# Main.net
KiCad netlist of a schematic drawn in Altium Designer
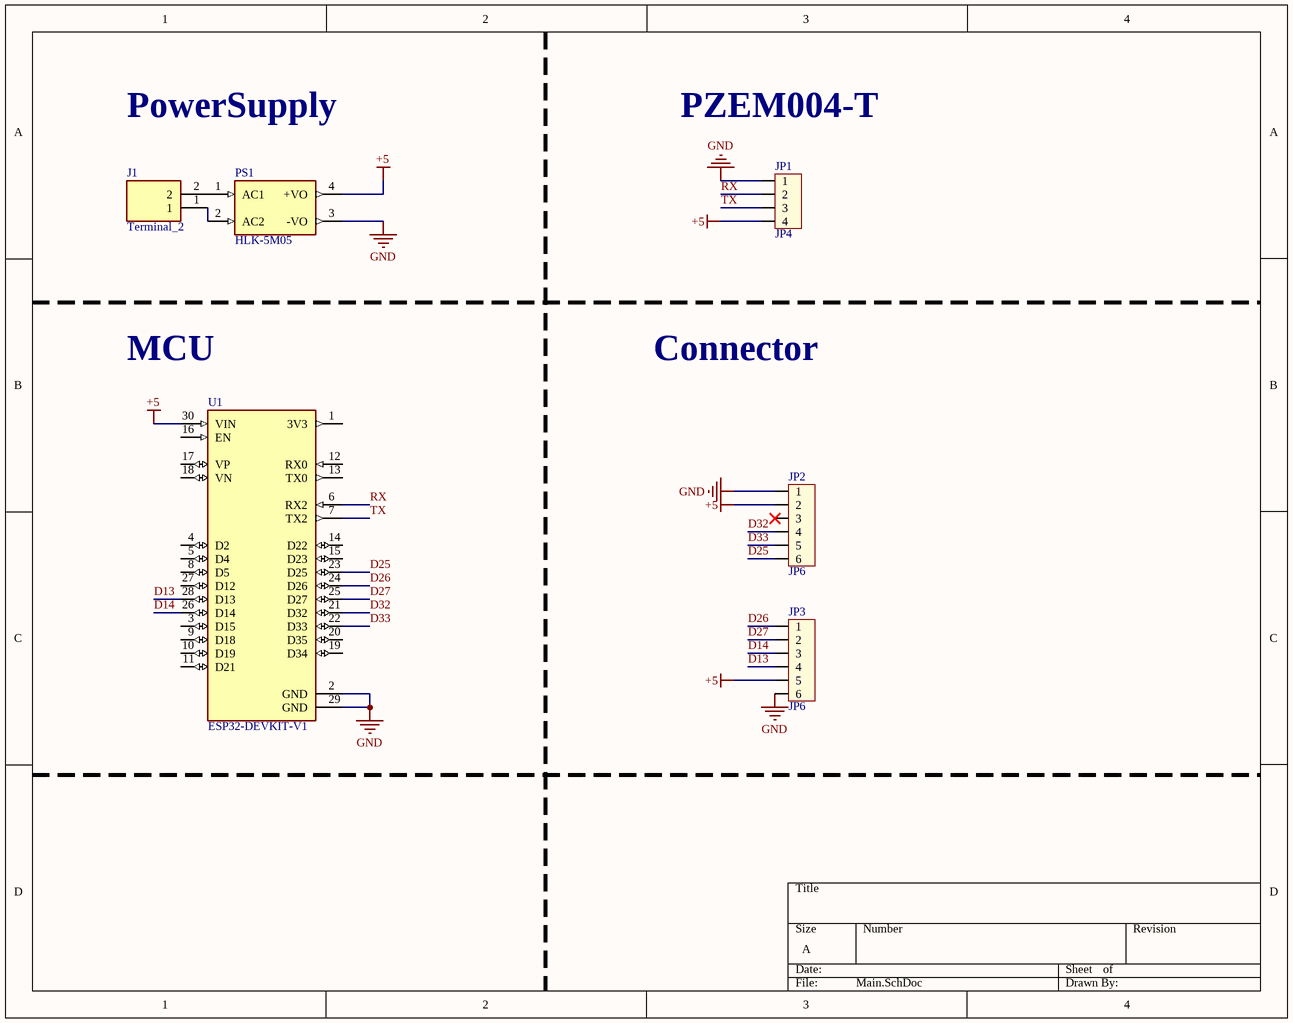
[diagram p0: Main.SchDoc]

(export (version "E")
  (design (tool "Eeschema 10.0.6"))
  (components
    (comp (ref "J1")
      (value "Terminal_2")
      (footprint "TE_282843-2")
      (fields (field (name "MP") "282843-2") (field (name "MF") "{'manufacturer': 'TE Connectivity'}"))
      (libsource (lib "282843-2") (part "282843-2"))
    )
    (comp (ref "JP1")
      (value "JP4")
      (footprint "CON4")
      (description "Connector 4")
      (libsource (lib "Kiet") (part "Con4"))
    )
    (comp (ref "JP2")
      (value "JP6")
      (footprint "CON6")
      (description "Connector 6")
      (libsource (lib "Kiet") (part "Con6"))
    )
    (comp (ref "JP3")
      (value "JP6")
      (footprint "CON6")
      (description "Connector 6")
      (libsource (lib "Kiet") (part "Con6"))
    )
    (comp (ref "PS1")
      (value "HLK-5M05")
      (footprint "CONV_HLK-5M05")
      (description "AC DC 220V to 5V 5W 5Watt Isolated Switching Step-Down Power Supply Module Converter")
      (fields (field (name "MF") "Hi-link"))
      (libsource (lib "HLK-5M05") (part "HLK-5M05"))
    )
    (comp (ref "U1")
      (value "ESP32-DEVKIT-V1")
      (footprint "MODULE_ESP32_DEVKIT_V1")
      (fields (field (name "MF") "Do it"))
      (libsource (lib "ESP32-DEVKIT-V1") (part "ESP32-DEVKIT-V1"))
    )
  )
  (nets
    (net (code "1") (name "+5") (class "Default")
      (node (ref "JP1") (pin "4") (pinfunction "4_4") (pintype "passive"))
      (node (ref "JP2") (pin "2") (pinfunction "2_2") (pintype "passive"))
      (node (ref "JP3") (pin "5") (pinfunction "5_5") (pintype "passive"))
      (node (ref "PS1") (pin "4") (pinfunction "+VO_4") (pintype "output"))
      (node (ref "U1") (pin "30") (pinfunction "VIN_30") (pintype "input"))
    )
    (net (code "2") (name "/D13") (class "Default")
      (node (ref "JP3") (pin "4") (pinfunction "4_4") (pintype "passive"))
      (node (ref "U1") (pin "28") (pinfunction "D13_28") (pintype "bidirectional"))
    )
    (net (code "3") (name "/D14") (class "Default")
      (node (ref "JP3") (pin "3") (pinfunction "3_3") (pintype "passive"))
      (node (ref "U1") (pin "26") (pinfunction "D14_26") (pintype "bidirectional"))
    )
    (net (code "4") (name "/D25") (class "Default")
      (node (ref "JP2") (pin "6") (pinfunction "6_6") (pintype "passive"))
      (node (ref "U1") (pin "23") (pinfunction "D25_23") (pintype "bidirectional"))
    )
    (net (code "5") (name "/D26") (class "Default")
      (node (ref "JP3") (pin "1") (pinfunction "1_1") (pintype "passive"))
      (node (ref "U1") (pin "24") (pinfunction "D26_24") (pintype "bidirectional"))
    )
    (net (code "6") (name "/D27") (class "Default")
      (node (ref "JP3") (pin "2") (pinfunction "2_2") (pintype "passive"))
      (node (ref "U1") (pin "25") (pinfunction "D27_25") (pintype "bidirectional"))
    )
    (net (code "7") (name "/D32") (class "Default")
      (node (ref "JP2") (pin "4") (pinfunction "4_4") (pintype "passive"))
      (node (ref "U1") (pin "21") (pinfunction "D32_21") (pintype "bidirectional"))
    )
    (net (code "8") (name "/D33") (class "Default")
      (node (ref "JP2") (pin "5") (pinfunction "5_5") (pintype "passive"))
      (node (ref "U1") (pin "22") (pinfunction "D33_22") (pintype "bidirectional"))
    )
    (net (code "9") (name "/RX") (class "Default")
      (node (ref "JP1") (pin "2") (pinfunction "2_2") (pintype "passive"))
      (node (ref "U1") (pin "6") (pinfunction "RX2_6") (pintype "input"))
    )
    (net (code "10") (name "/TX") (class "Default")
      (node (ref "JP1") (pin "3") (pinfunction "3_3") (pintype "passive"))
      (node (ref "U1") (pin "7") (pinfunction "TX2_7") (pintype "output"))
    )
    (net (code "11") (name "GND") (class "Default")
      (node (ref "JP1") (pin "1") (pinfunction "1_1") (pintype "passive"))
      (node (ref "JP2") (pin "1") (pinfunction "1_1") (pintype "passive"))
      (node (ref "JP3") (pin "6") (pinfunction "6_6") (pintype "passive"))
      (node (ref "PS1") (pin "3") (pinfunction "-VO_3") (pintype "output"))
      (node (ref "U1") (pin "2") (pinfunction "GND_2") (pintype "power_in"))
      (node (ref "U1") (pin "29") (pinfunction "GND_29") (pintype "power_in"))
    )
    (net (code "12") (name "Net-(PS1-AC1)") (class "Default")
      (node (ref "J1") (pin "2") (pinfunction "2_2") (pintype "passive"))
      (node (ref "PS1") (pin "1") (pinfunction "AC1_1") (pintype "input"))
    )
    (net (code "13") (name "Net-(PS1-AC2)") (class "Default")
      (node (ref "J1") (pin "1") (pinfunction "1_1") (pintype "passive"))
      (node (ref "PS1") (pin "2") (pinfunction "AC2_2") (pintype "input"))
    )
    (net (code "14") (name "unconnected-(JP2-Pad3)") (class "Default")
      (node (ref "JP2") (pin "3") (pinfunction "3_3") (pintype "passive+no_connect"))
    )
    (net (code "15") (name "unconnected-(U1-3V3-Pad1)") (class "Default")
      (node (ref "U1") (pin "1") (pinfunction "3V3_1") (pintype "output"))
    )
    (net (code "16") (name "unconnected-(U1-D2-Pad4)") (class "Default")
      (node (ref "U1") (pin "4") (pinfunction "D2_4") (pintype "bidirectional"))
    )
    (net (code "17") (name "unconnected-(U1-D4-Pad5)") (class "Default")
      (node (ref "U1") (pin "5") (pinfunction "D4_5") (pintype "bidirectional"))
    )
    (net (code "18") (name "unconnected-(U1-D5-Pad8)") (class "Default")
      (node (ref "U1") (pin "8") (pinfunction "D5_8") (pintype "bidirectional"))
    )
    (net (code "19") (name "unconnected-(U1-D12-Pad27)") (class "Default")
      (node (ref "U1") (pin "27") (pinfunction "D12_27") (pintype "bidirectional"))
    )
    (net (code "20") (name "unconnected-(U1-D15-Pad3)") (class "Default")
      (node (ref "U1") (pin "3") (pinfunction "D15_3") (pintype "bidirectional"))
    )
    (net (code "21") (name "unconnected-(U1-D18-Pad9)") (class "Default")
      (node (ref "U1") (pin "9") (pinfunction "D18_9") (pintype "bidirectional"))
    )
    (net (code "22") (name "unconnected-(U1-D19-Pad10)") (class "Default")
      (node (ref "U1") (pin "10") (pinfunction "D19_10") (pintype "bidirectional"))
    )
    (net (code "23") (name "unconnected-(U1-D21-Pad11)") (class "Default")
      (node (ref "U1") (pin "11") (pinfunction "D21_11") (pintype "bidirectional"))
    )
    (net (code "24") (name "unconnected-(U1-D22-Pad14)") (class "Default")
      (node (ref "U1") (pin "14") (pinfunction "D22_14") (pintype "bidirectional"))
    )
    (net (code "25") (name "unconnected-(U1-D23-Pad15)") (class "Default")
      (node (ref "U1") (pin "15") (pinfunction "D23_15") (pintype "bidirectional"))
    )
    (net (code "26") (name "unconnected-(U1-D34-Pad19)") (class "Default")
      (node (ref "U1") (pin "19") (pinfunction "D34_19") (pintype "bidirectional"))
    )
    (net (code "27") (name "unconnected-(U1-D35-Pad20)") (class "Default")
      (node (ref "U1") (pin "20") (pinfunction "D35_20") (pintype "bidirectional"))
    )
    (net (code "28") (name "unconnected-(U1-EN-Pad16)") (class "Default")
      (node (ref "U1") (pin "16") (pinfunction "EN_16") (pintype "input"))
    )
    (net (code "29") (name "unconnected-(U1-RX0-Pad12)") (class "Default")
      (node (ref "U1") (pin "12") (pinfunction "RX0_12") (pintype "input"))
    )
    (net (code "30") (name "unconnected-(U1-TX0-Pad13)") (class "Default")
      (node (ref "U1") (pin "13") (pinfunction "TX0_13") (pintype "output"))
    )
    (net (code "31") (name "unconnected-(U1-VN-Pad18)") (class "Default")
      (node (ref "U1") (pin "18") (pinfunction "VN_18") (pintype "bidirectional"))
    )
    (net (code "32") (name "unconnected-(U1-VP-Pad17)") (class "Default")
      (node (ref "U1") (pin "17") (pinfunction "VP_17") (pintype "bidirectional"))
    )
  )
)
